# BLDC_driver_board_4_layer.net
KiCad netlist of a schematic drawn in EAGLE
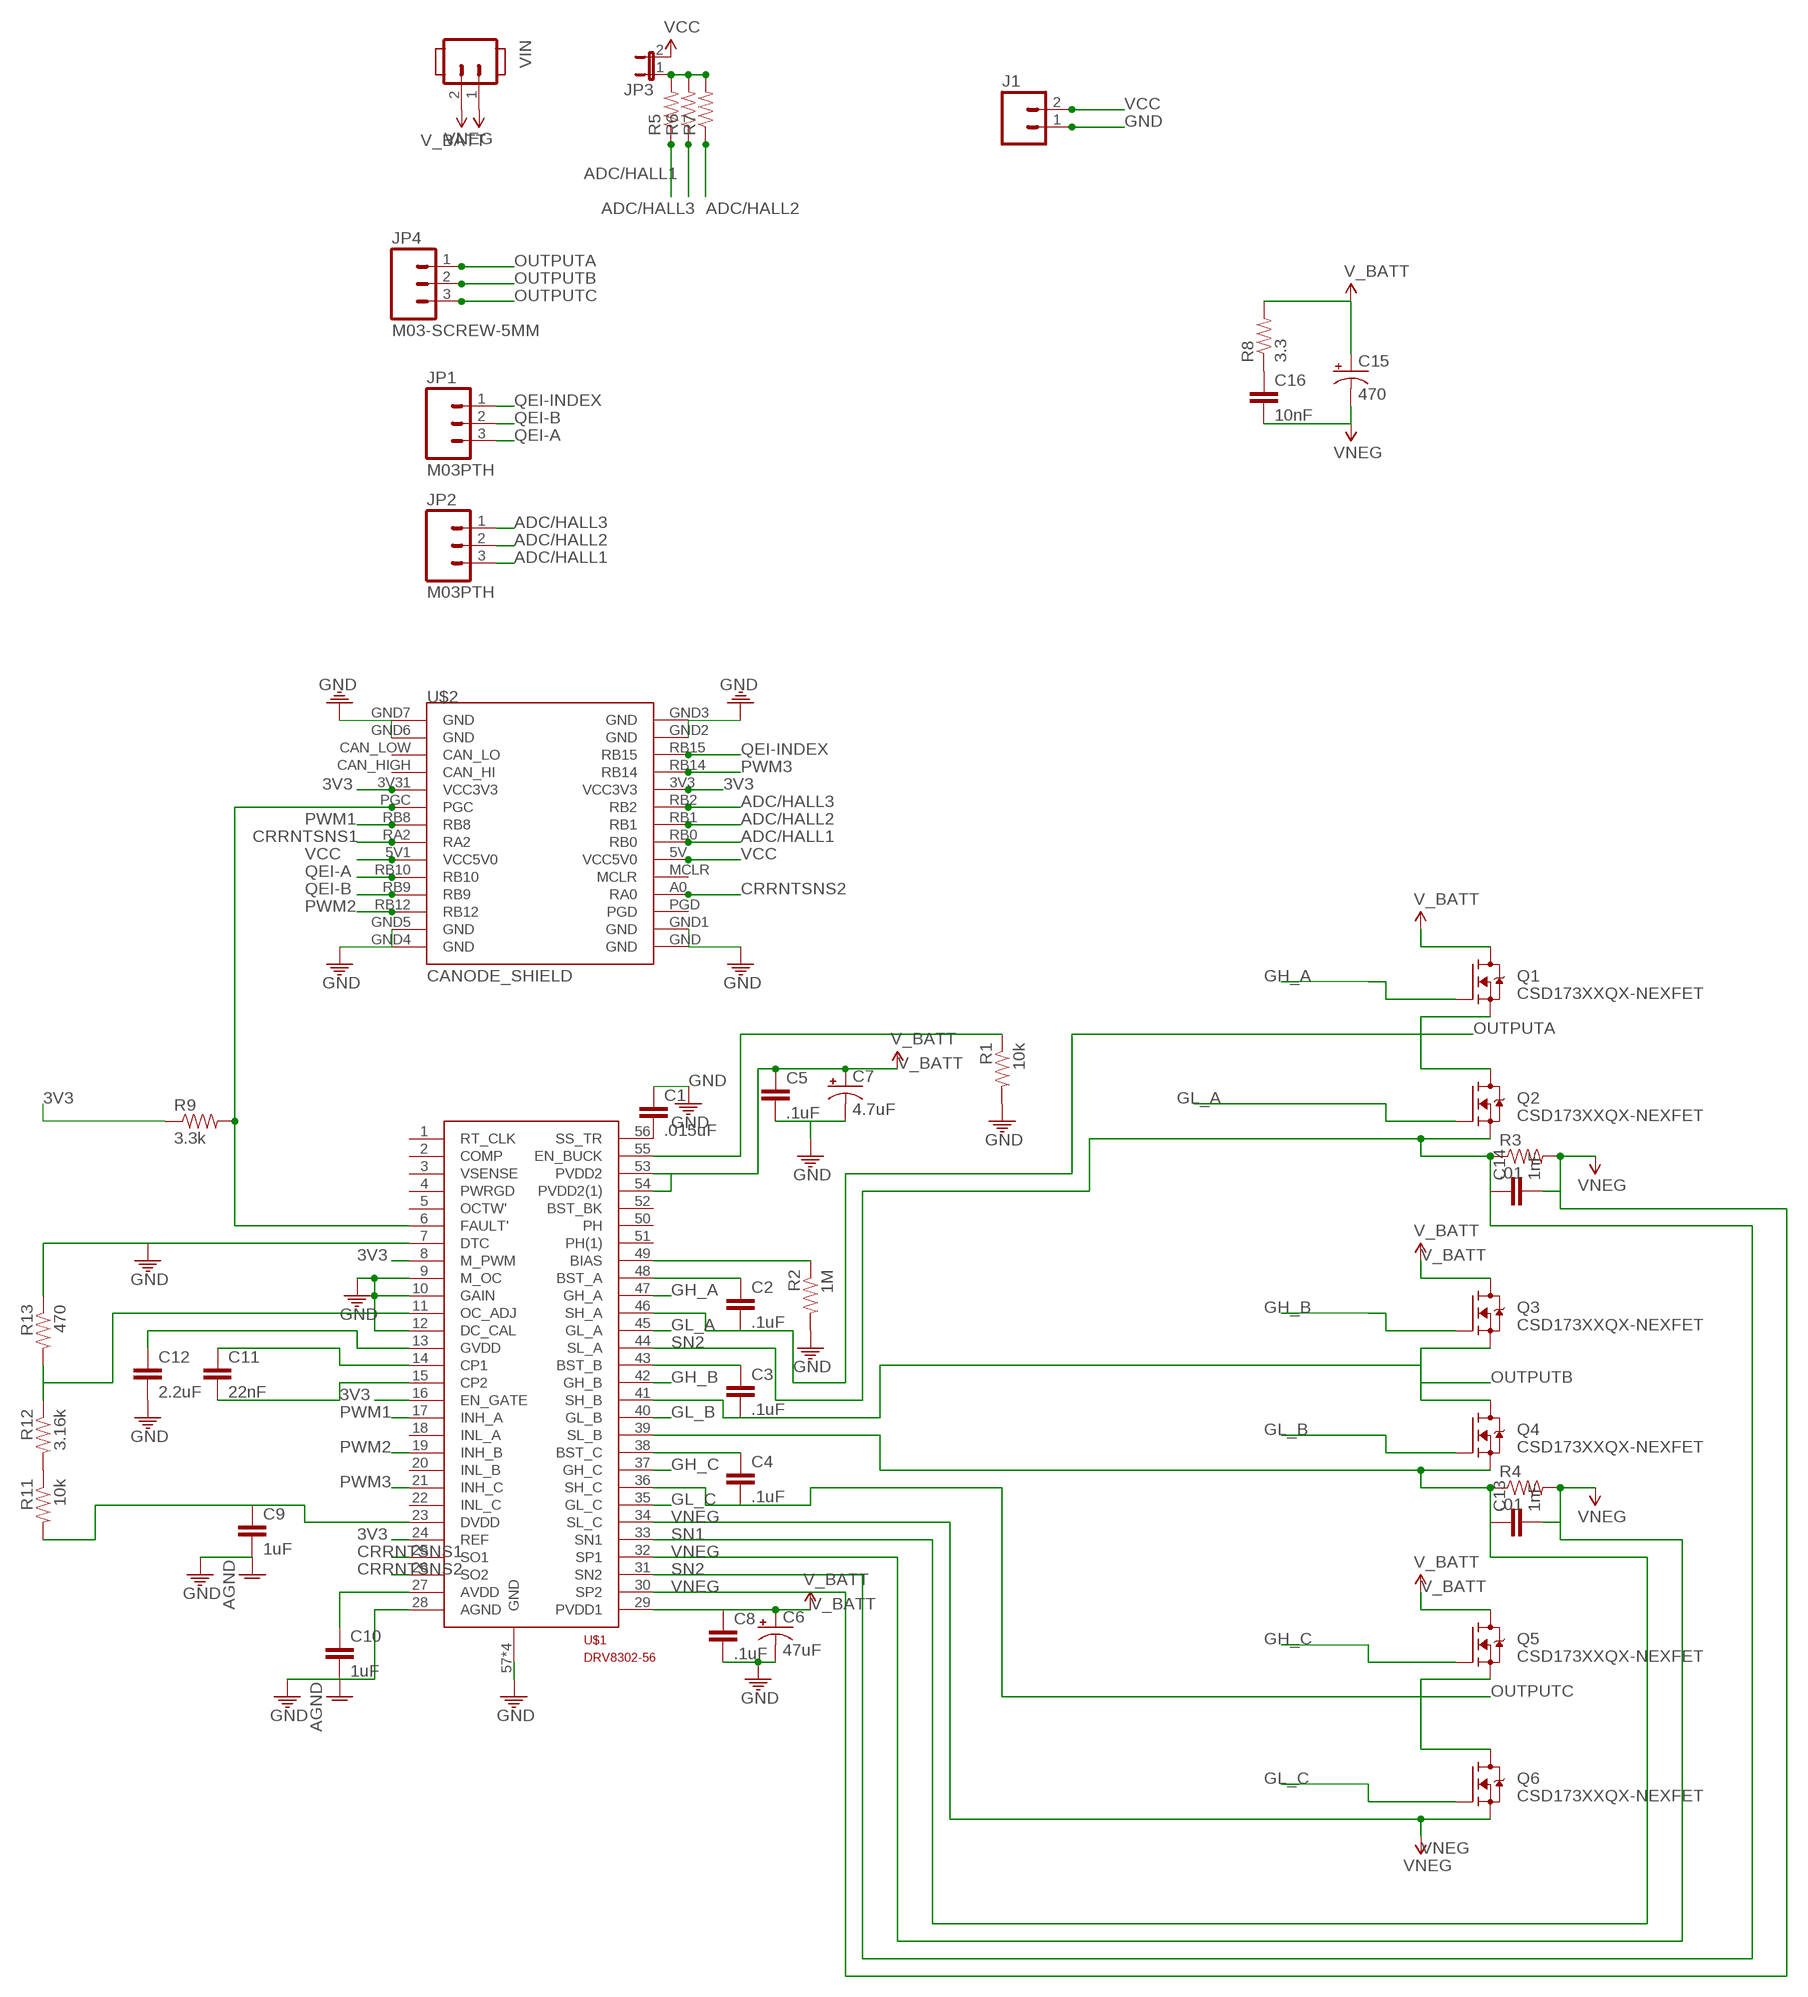
[diagram p0: schematic, sheet 1]

(export (version "E")
  (design (tool "Eeschema 10.0.6"))
  (components
    (comp (ref "C1")
      (value ".015uF")
      (footprint "eagle-import:1206")
      (libsource (lib "eagle-import") (part "CAP1206"))
    )
    (comp (ref "C2")
      (value ".1uF")
      (footprint "eagle-import:1206")
      (libsource (lib "eagle-import") (part "CAP1206"))
    )
    (comp (ref "C3")
      (value ".1uF")
      (footprint "eagle-import:1206")
      (libsource (lib "eagle-import") (part "CAP1206"))
    )
    (comp (ref "C4")
      (value ".1uF")
      (footprint "eagle-import:1206")
      (libsource (lib "eagle-import") (part "CAP1206"))
    )
    (comp (ref "C5")
      (value ".1uF")
      (footprint "eagle-import:1206")
      (libsource (lib "eagle-import") (part "CAP1206"))
    )
    (comp (ref "C6")
      (value "47uF")
      (footprint "eagle-import:CPOL-RADIAL-6.3MM")
      (libsource (lib "eagle-import") (part "pavlo_CAP_POL"))
    )
    (comp (ref "C7")
      (value "4.7uF")
      (footprint "eagle-import:CPOL-RADIA-5MM")
      (libsource (lib "eagle-import") (part "CAP_POLYO"))
    )
    (comp (ref "C8")
      (value ".1uF")
      (footprint "eagle-import:1206")
      (libsource (lib "eagle-import") (part "CAP1206"))
    )
    (comp (ref "C9")
      (value "1uF")
      (footprint "eagle-import:1206")
      (libsource (lib "eagle-import") (part "CAP1206"))
    )
    (comp (ref "C10")
      (value "1uF")
      (footprint "eagle-import:1206")
      (libsource (lib "eagle-import") (part "CAP1206"))
    )
    (comp (ref "C11")
      (value "22nF")
      (footprint "eagle-import:1206")
      (libsource (lib "eagle-import") (part "CAP1206"))
    )
    (comp (ref "C12")
      (value "2.2uF")
      (footprint "eagle-import:1206")
      (libsource (lib "eagle-import") (part "CAP1206"))
    )
    (comp (ref "C13")
      (value "1nF")
      (footprint "eagle-import:1206")
      (libsource (lib "eagle-import") (part "CAP1206"))
    )
    (comp (ref "C14")
      (value "1nF")
      (footprint "eagle-import:1206")
      (libsource (lib "eagle-import") (part "CAP1206"))
    )
    (comp (ref "C15")
      (value "470")
      (footprint "eagle-import:CPOL-RADIAL-1000UF-63V")
      (libsource (lib "eagle-import") (part "CAP_POLPTH3"))
    )
    (comp (ref "C16")
      (value "10nF")
      (footprint "eagle-import:1206")
      (libsource (lib "eagle-import") (part "CAP1206"))
    )
    (comp (ref "J1")
      (value "M02")
      (footprint "eagle-import:SOCKET-MALE-2.54MM-2")
      (libsource (lib "eagle-import") (part "M02"))
    )
    (comp (ref "JP1")
      (value "M03PTH")
      (footprint "eagle-import:1X03")
      (libsource (lib "eagle-import") (part "M03PTH"))
    )
    (comp (ref "JP2")
      (value "M03PTH")
      (footprint "eagle-import:1X03")
      (libsource (lib "eagle-import") (part "M03PTH"))
    )
    (comp (ref "JP3")
      (value "JP1E")
      (footprint "eagle-import:JP1")
      (libsource (lib "eagle-import") (part "JP1E"))
    )
    (comp (ref "JP4")
      (value "M03-SCREW-5MM")
      (footprint "eagle-import:SCREWTERMINAL-5MM-3")
      (libsource (lib "eagle-import") (part "M03-SCREW-5MM"))
    )
    (comp (ref "Q1")
      (value "CSD173XXQX-NEXFET")
      (footprint "eagle-import:CSD173XXQX")
      (libsource (lib "eagle-import") (part "CSD173XXQX-NEXFET"))
    )
    (comp (ref "Q2")
      (value "CSD173XXQX-NEXFET")
      (footprint "eagle-import:CSD173XXQX")
      (libsource (lib "eagle-import") (part "CSD173XXQX-NEXFET"))
    )
    (comp (ref "Q3")
      (value "CSD173XXQX-NEXFET")
      (footprint "eagle-import:CSD173XXQX")
      (libsource (lib "eagle-import") (part "CSD173XXQX-NEXFET"))
    )
    (comp (ref "Q4")
      (value "CSD173XXQX-NEXFET")
      (footprint "eagle-import:CSD173XXQX")
      (libsource (lib "eagle-import") (part "CSD173XXQX-NEXFET"))
    )
    (comp (ref "Q5")
      (value "CSD173XXQX-NEXFET")
      (footprint "eagle-import:CSD173XXQX")
      (libsource (lib "eagle-import") (part "CSD173XXQX-NEXFET"))
    )
    (comp (ref "Q6")
      (value "CSD173XXQX-NEXFET")
      (footprint "eagle-import:CSD173XXQX")
      (libsource (lib "eagle-import") (part "CSD173XXQX-NEXFET"))
    )
    (comp (ref "R1")
      (value "10k")
      (footprint "eagle-import:0805")
      (libsource (lib "eagle-import") (part "RESISTOR0805-RES"))
    )
    (comp (ref "R2")
      (value "1M")
      (footprint "eagle-import:0805")
      (libsource (lib "eagle-import") (part "RESISTOR0805-RES"))
    )
    (comp (ref "R3")
      (value ".01")
      (footprint "eagle-import:SMT-REF")
      (libsource (lib "eagle-import") (part "RESISTOR"))
    )
    (comp (ref "R4")
      (value ".01")
      (footprint "eagle-import:SMT-REF")
      (libsource (lib "eagle-import") (part "RESISTOR"))
    )
    (comp (ref "R5")
      (value "RESISTOR0805-RES")
      (footprint "eagle-import:0805")
      (libsource (lib "eagle-import") (part "RESISTOR0805-RES"))
    )
    (comp (ref "R6")
      (value "RESISTOR0805-RES")
      (footprint "eagle-import:0805")
      (libsource (lib "eagle-import") (part "RESISTOR0805-RES"))
    )
    (comp (ref "R7")
      (value "RESISTOR0805-RES")
      (footprint "eagle-import:0805")
      (libsource (lib "eagle-import") (part "RESISTOR0805-RES"))
    )
    (comp (ref "R8")
      (value "3.3")
      (footprint "eagle-import:1206")
      (libsource (lib "eagle-import") (part "CMPE118lib_RESISTOR1206"))
    )
    (comp (ref "R9")
      (value "3.3k")
      (footprint "eagle-import:0805")
      (libsource (lib "eagle-import") (part "RESISTOR0805-RES"))
    )
    (comp (ref "R11")
      (value "10k")
      (footprint "eagle-import:0805")
      (libsource (lib "eagle-import") (part "RESISTOR0805-RES"))
    )
    (comp (ref "R12")
      (value "3.16k")
      (footprint "eagle-import:0805")
      (libsource (lib "eagle-import") (part "RESISTOR0805-RES"))
    )
    (comp (ref "R13")
      (value "470")
      (footprint "eagle-import:0805")
      (libsource (lib "eagle-import") (part "RESISTOR0805-RES"))
    )
    (comp (ref "U$1")
      (value "DRV8302-56")
      (footprint "eagle-import:HTSSOP56")
      (libsource (lib "eagle-import") (part "DRV8302-56"))
    )
    (comp (ref "U$2")
      (value "CANODE_SHIELD")
      (footprint "eagle-import:CANODE_SHIELD")
      (libsource (lib "eagle-import") (part "CANODE_SHIELD"))
    )
    (comp (ref "VIN")
      (value "SCREWTERM02")
      (footprint "eagle-import:SCREW_TERMINAL-5.08MM-2")
      (libsource (lib "eagle-import") (part "SCREWTERM02"))
    )
  )
  (nets
    (net (code "1") (name "/3V3") (class "Default")
      (node (ref "R9") (pin "1") (pinfunction "1_1") (pintype "passive"))
      (node (ref "U$1") (pin "16") (pinfunction "EN_GATE_16") (pintype "bidirectional"))
      (node (ref "U$1") (pin "24") (pinfunction "REF_24") (pintype "bidirectional"))
      (node (ref "U$1") (pin "8") (pinfunction "M_PWM_8") (pintype "bidirectional"))
      (node (ref "U$2") (pin "3V3") (pinfunction "VCC3V3_3V3") (pintype "bidirectional"))
      (node (ref "U$2") (pin "3V31") (pinfunction "VCC3V3_3V31") (pintype "bidirectional"))
    )
    (net (code "2") (name "/ADC{slash}HALL1") (class "Default")
      (node (ref "JP2") (pin "3") (pinfunction "3_3") (pintype "passive"))
      (node (ref "R6") (pin "1") (pinfunction "1_1") (pintype "passive"))
      (node (ref "U$2") (pin "RB0") (pinfunction "RB0_RB0") (pintype "bidirectional"))
    )
    (net (code "3") (name "/ADC{slash}HALL2") (class "Default")
      (node (ref "JP2") (pin "2") (pinfunction "2_2") (pintype "passive"))
      (node (ref "R7") (pin "1") (pinfunction "1_1") (pintype "passive"))
      (node (ref "U$2") (pin "RB1") (pinfunction "RB1_RB1") (pintype "bidirectional"))
    )
    (net (code "4") (name "/ADC{slash}HALL3") (class "Default")
      (node (ref "JP2") (pin "1") (pinfunction "1_1") (pintype "passive"))
      (node (ref "R5") (pin "1") (pinfunction "1_1") (pintype "passive"))
      (node (ref "U$2") (pin "RB2") (pinfunction "RB2_RB2") (pintype "bidirectional"))
    )
    (net (code "5") (name "/CRRNTSNS1") (class "Default")
      (node (ref "U$1") (pin "25") (pinfunction "SO1_25") (pintype "bidirectional"))
      (node (ref "U$2") (pin "RA2") (pinfunction "RA2_RA2") (pintype "bidirectional"))
    )
    (net (code "6") (name "/CRRNTSNS2") (class "Default")
      (node (ref "U$1") (pin "26") (pinfunction "SO2_26") (pintype "bidirectional"))
      (node (ref "U$2") (pin "A0") (pinfunction "RA0_A0") (pintype "bidirectional"))
    )
    (net (code "7") (name "/GH_A") (class "Default")
      (node (ref "Q1") (pin "G") (pinfunction "G_G") (pintype "passive"))
      (node (ref "U$1") (pin "47") (pinfunction "GH_A_47") (pintype "bidirectional"))
    )
    (net (code "8") (name "/GH_B") (class "Default")
      (node (ref "Q3") (pin "G") (pinfunction "G_G") (pintype "passive"))
      (node (ref "U$1") (pin "42") (pinfunction "GH_B_42") (pintype "bidirectional"))
    )
    (net (code "9") (name "/GH_C") (class "Default")
      (node (ref "Q5") (pin "G") (pinfunction "G_G") (pintype "passive"))
      (node (ref "U$1") (pin "37") (pinfunction "GH_C_37") (pintype "bidirectional"))
    )
    (net (code "10") (name "/GL_A") (class "Default")
      (node (ref "Q2") (pin "G") (pinfunction "G_G") (pintype "passive"))
      (node (ref "U$1") (pin "45") (pinfunction "GL_A_45") (pintype "bidirectional"))
    )
    (net (code "11") (name "/GL_B") (class "Default")
      (node (ref "Q4") (pin "G") (pinfunction "G_G") (pintype "passive"))
      (node (ref "U$1") (pin "40") (pinfunction "GL_B_40") (pintype "bidirectional"))
    )
    (net (code "12") (name "/GL_C") (class "Default")
      (node (ref "Q6") (pin "G") (pinfunction "G_G") (pintype "passive"))
      (node (ref "U$1") (pin "35") (pinfunction "GL_C_35") (pintype "bidirectional"))
    )
    (net (code "13") (name "/OUTPUTA") (class "Default")
      (node (ref "C2") (pin "2") (pinfunction "2_2") (pintype "passive"))
      (node (ref "JP4") (pin "1") (pinfunction "1_1") (pintype "passive"))
      (node (ref "Q1") (pin "S1") (pinfunction "S_S1") (pintype "passive"))
      (node (ref "Q1") (pin "S2") (pinfunction "S_S2") (pintype "passive"))
      (node (ref "Q1") (pin "S3") (pinfunction "S_S3") (pintype "passive"))
      (node (ref "Q2") (pin "D") (pinfunction "D_D") (pintype "passive"))
      (node (ref "Q2") (pin "P$1") (pinfunction "D_P$1") (pintype "passive"))
      (node (ref "Q2") (pin "P$2") (pinfunction "D_P$2") (pintype "passive"))
      (node (ref "Q2") (pin "P$3") (pinfunction "D_P$3") (pintype "passive"))
      (node (ref "Q2") (pin "P$4") (pinfunction "D_P$4") (pintype "passive"))
      (node (ref "Q2") (pin "P$5") (pinfunction "D_P$5") (pintype "passive"))
      (node (ref "Q2") (pin "P$6") (pinfunction "D_P$6") (pintype "passive"))
      (node (ref "Q2") (pin "P$7") (pinfunction "D_P$7") (pintype "passive"))
      (node (ref "Q2") (pin "P$8") (pinfunction "D_P$8") (pintype "passive"))
      (node (ref "Q2") (pin "P$9") (pinfunction "D_P$9") (pintype "passive"))
      (node (ref "U$1") (pin "46") (pinfunction "SH_A_46") (pintype "bidirectional"))
    )
    (net (code "14") (name "/OUTPUTB") (class "Default")
      (node (ref "C3") (pin "2") (pinfunction "2_2") (pintype "passive"))
      (node (ref "JP4") (pin "2") (pinfunction "2_2") (pintype "passive"))
      (node (ref "Q3") (pin "S1") (pinfunction "S_S1") (pintype "passive"))
      (node (ref "Q3") (pin "S2") (pinfunction "S_S2") (pintype "passive"))
      (node (ref "Q3") (pin "S3") (pinfunction "S_S3") (pintype "passive"))
      (node (ref "Q4") (pin "D") (pinfunction "D_D") (pintype "passive"))
      (node (ref "Q4") (pin "P$1") (pinfunction "D_P$1") (pintype "passive"))
      (node (ref "Q4") (pin "P$2") (pinfunction "D_P$2") (pintype "passive"))
      (node (ref "Q4") (pin "P$3") (pinfunction "D_P$3") (pintype "passive"))
      (node (ref "Q4") (pin "P$4") (pinfunction "D_P$4") (pintype "passive"))
      (node (ref "Q4") (pin "P$5") (pinfunction "D_P$5") (pintype "passive"))
      (node (ref "Q4") (pin "P$6") (pinfunction "D_P$6") (pintype "passive"))
      (node (ref "Q4") (pin "P$7") (pinfunction "D_P$7") (pintype "passive"))
      (node (ref "Q4") (pin "P$8") (pinfunction "D_P$8") (pintype "passive"))
      (node (ref "Q4") (pin "P$9") (pinfunction "D_P$9") (pintype "passive"))
      (node (ref "U$1") (pin "41") (pinfunction "SH_B_41") (pintype "bidirectional"))
    )
    (net (code "15") (name "/OUTPUTC") (class "Default")
      (node (ref "C4") (pin "2") (pinfunction "2_2") (pintype "passive"))
      (node (ref "JP4") (pin "3") (pinfunction "3_3") (pintype "passive"))
      (node (ref "Q5") (pin "S1") (pinfunction "S_S1") (pintype "passive"))
      (node (ref "Q5") (pin "S2") (pinfunction "S_S2") (pintype "passive"))
      (node (ref "Q5") (pin "S3") (pinfunction "S_S3") (pintype "passive"))
      (node (ref "Q6") (pin "D") (pinfunction "D_D") (pintype "passive"))
      (node (ref "Q6") (pin "P$1") (pinfunction "D_P$1") (pintype "passive"))
      (node (ref "Q6") (pin "P$2") (pinfunction "D_P$2") (pintype "passive"))
      (node (ref "Q6") (pin "P$3") (pinfunction "D_P$3") (pintype "passive"))
      (node (ref "Q6") (pin "P$4") (pinfunction "D_P$4") (pintype "passive"))
      (node (ref "Q6") (pin "P$5") (pinfunction "D_P$5") (pintype "passive"))
      (node (ref "Q6") (pin "P$6") (pinfunction "D_P$6") (pintype "passive"))
      (node (ref "Q6") (pin "P$7") (pinfunction "D_P$7") (pintype "passive"))
      (node (ref "Q6") (pin "P$8") (pinfunction "D_P$8") (pintype "passive"))
      (node (ref "Q6") (pin "P$9") (pinfunction "D_P$9") (pintype "passive"))
      (node (ref "U$1") (pin "36") (pinfunction "SH_C_36") (pintype "bidirectional"))
    )
    (net (code "16") (name "/PWM1") (class "Default")
      (node (ref "U$1") (pin "17") (pinfunction "INH_A_17") (pintype "bidirectional"))
      (node (ref "U$2") (pin "RB8") (pinfunction "RB8_RB8") (pintype "bidirectional"))
    )
    (net (code "17") (name "/PWM2") (class "Default")
      (node (ref "U$1") (pin "19") (pinfunction "INH_B_19") (pintype "bidirectional"))
      (node (ref "U$2") (pin "RB12") (pinfunction "RB12_RB12") (pintype "bidirectional"))
    )
    (net (code "18") (name "/PWM3") (class "Default")
      (node (ref "U$1") (pin "21") (pinfunction "INH_C_21") (pintype "bidirectional"))
      (node (ref "U$2") (pin "RB14") (pinfunction "RB14_RB14") (pintype "bidirectional"))
    )
    (net (code "19") (name "/QEI-A") (class "Default")
      (node (ref "JP1") (pin "3") (pinfunction "3_3") (pintype "passive"))
      (node (ref "U$2") (pin "RB10") (pinfunction "RB10_RB10") (pintype "bidirectional"))
    )
    (net (code "20") (name "/QEI-B") (class "Default")
      (node (ref "JP1") (pin "2") (pinfunction "2_2") (pintype "passive"))
      (node (ref "U$2") (pin "RB9") (pinfunction "RB9_RB9") (pintype "bidirectional"))
    )
    (net (code "21") (name "/QEI-INDEX") (class "Default")
      (node (ref "JP1") (pin "1") (pinfunction "1_1") (pintype "passive"))
      (node (ref "U$2") (pin "RB15") (pinfunction "RB15_RB15") (pintype "bidirectional"))
    )
    (net (code "22") (name "/SN1") (class "Default")
      (node (ref "C13") (pin "1") (pinfunction "1_1") (pintype "passive"))
      (node (ref "Q4") (pin "S1") (pinfunction "S_S1") (pintype "passive"))
      (node (ref "Q4") (pin "S2") (pinfunction "S_S2") (pintype "passive"))
      (node (ref "Q4") (pin "S3") (pinfunction "S_S3") (pintype "passive"))
      (node (ref "R4") (pin "1") (pinfunction "1_1") (pintype "passive"))
      (node (ref "R4") (pin "P$10") (pinfunction "1_P$10") (pintype "passive"))
      (node (ref "R4") (pin "P$11") (pinfunction "1_P$11") (pintype "passive"))
      (node (ref "R4") (pin "P$12") (pinfunction "1_P$12") (pintype "passive"))
      (node (ref "R4") (pin "P$7") (pinfunction "1_P$7") (pintype "passive"))
      (node (ref "R4") (pin "P$8") (pinfunction "1_P$8") (pintype "passive"))
      (node (ref "R4") (pin "P$9") (pinfunction "1_P$9") (pintype "passive"))
      (node (ref "U$1") (pin "33") (pinfunction "SN1_33") (pintype "bidirectional"))
      (node (ref "U$1") (pin "39") (pinfunction "SL_B_39") (pintype "bidirectional"))
    )
    (net (code "23") (name "/SN2") (class "Default")
      (node (ref "C14") (pin "1") (pinfunction "1_1") (pintype "passive"))
      (node (ref "Q2") (pin "S1") (pinfunction "S_S1") (pintype "passive"))
      (node (ref "Q2") (pin "S2") (pinfunction "S_S2") (pintype "passive"))
      (node (ref "Q2") (pin "S3") (pinfunction "S_S3") (pintype "passive"))
      (node (ref "R3") (pin "1") (pinfunction "1_1") (pintype "passive"))
      (node (ref "R3") (pin "P$10") (pinfunction "1_P$10") (pintype "passive"))
      (node (ref "R3") (pin "P$11") (pinfunction "1_P$11") (pintype "passive"))
      (node (ref "R3") (pin "P$12") (pinfunction "1_P$12") (pintype "passive"))
      (node (ref "R3") (pin "P$7") (pinfunction "1_P$7") (pintype "passive"))
      (node (ref "R3") (pin "P$8") (pinfunction "1_P$8") (pintype "passive"))
      (node (ref "R3") (pin "P$9") (pinfunction "1_P$9") (pintype "passive"))
      (node (ref "U$1") (pin "31") (pinfunction "SN2_31") (pintype "bidirectional"))
      (node (ref "U$1") (pin "44") (pinfunction "SL_A_44") (pintype "bidirectional"))
    )
    (net (code "24") (name "AGND") (class "Default")
      (node (ref "C1") (pin "1") (pinfunction "1_1") (pintype "passive"))
      (node (ref "C10") (pin "2") (pinfunction "2_2") (pintype "passive"))
      (node (ref "C12") (pin "2") (pinfunction "2_2") (pintype "passive"))
      (node (ref "C5") (pin "2") (pinfunction "2_2") (pintype "passive"))
      (node (ref "C6") (pin "2") (pinfunction "-_2") (pintype "passive"))
      (node (ref "C7") (pin "2") (pinfunction "-_2") (pintype "passive"))
      (node (ref "C8") (pin "2") (pinfunction "2_2") (pintype "passive"))
      (node (ref "C9") (pin "2") (pinfunction "2_2") (pintype "passive"))
      (node (ref "J1") (pin "1") (pinfunction "1_1") (pintype "passive"))
      (node (ref "R1") (pin "2") (pinfunction "2_2") (pintype "passive"))
      (node (ref "R13") (pin "1") (pinfunction "1_1") (pintype "passive"))
      (node (ref "R2") (pin "2") (pinfunction "2_2") (pintype "passive"))
      (node (ref "U$1") (pin "10") (pinfunction "GAIN_10") (pintype "bidirectional"))
      (node (ref "U$1") (pin "12") (pinfunction "DC_CAL_12") (pintype "bidirectional"))
      (node (ref "U$1") (pin "28") (pinfunction "AGND_28") (pintype "bidirectional"))
      (node (ref "U$1") (pin "57") (pinfunction "GND_57") (pintype "bidirectional"))
      (node (ref "U$1") (pin "7") (pinfunction "DTC_7") (pintype "bidirectional"))
      (node (ref "U$1") (pin "9") (pinfunction "M_OC_9") (pintype "bidirectional"))
      (node (ref "U$1") (pin "P$1") (pinfunction "GND_P$1") (pintype "bidirectional"))
      (node (ref "U$1") (pin "P$2") (pinfunction "GND_P$2") (pintype "bidirectional"))
      (node (ref "U$1") (pin "P$3") (pinfunction "GND_P$3") (pintype "bidirectional"))
      (node (ref "U$2") (pin "GND") (pinfunction "GND_GND") (pintype "bidirectional"))
      (node (ref "U$2") (pin "GND1") (pinfunction "GND_GND1") (pintype "bidirectional"))
      (node (ref "U$2") (pin "GND2") (pinfunction "GND_GND2") (pintype "bidirectional"))
      (node (ref "U$2") (pin "GND3") (pinfunction "GND_GND3") (pintype "bidirectional"))
      (node (ref "U$2") (pin "GND4") (pinfunction "GND_GND4") (pintype "bidirectional"))
      (node (ref "U$2") (pin "GND5") (pinfunction "GND_GND5") (pintype "bidirectional"))
      (node (ref "U$2") (pin "GND6") (pinfunction "GND_GND6") (pintype "bidirectional"))
      (node (ref "U$2") (pin "GND7") (pinfunction "GND_GND7") (pintype "bidirectional"))
    )
    (net (code "25") (name "Net-(C16-Pad1)") (class "Default")
      (node (ref "C16") (pin "1") (pinfunction "1_1") (pintype "passive"))
      (node (ref "R8") (pin "1") (pinfunction "1_1") (pintype "passive"))
    )
    (net (code "26") (name "Net-(JP3-Pad1)") (class "Default")
      (node (ref "JP3") (pin "1") (pinfunction "1_1") (pintype "passive"))
      (node (ref "R5") (pin "2") (pinfunction "2_2") (pintype "passive"))
      (node (ref "R6") (pin "2") (pinfunction "2_2") (pintype "passive"))
      (node (ref "R7") (pin "2") (pinfunction "2_2") (pintype "passive"))
    )
    (net (code "27") (name "Net-(R11-Pad1)") (class "Default")
      (node (ref "R11") (pin "1") (pinfunction "1_1") (pintype "passive"))
      (node (ref "R12") (pin "2") (pinfunction "2_2") (pintype "passive"))
    )
    (net (code "28") (name "Net-(U$1-AVDD)") (class "Default")
      (node (ref "C10") (pin "1") (pinfunction "1_1") (pintype "passive"))
      (node (ref "U$1") (pin "27") (pinfunction "AVDD_27") (pintype "bidirectional"))
    )
    (net (code "29") (name "Net-(U$1-BIAS)") (class "Default")
      (node (ref "R2") (pin "1") (pinfunction "1_1") (pintype "passive"))
      (node (ref "U$1") (pin "49") (pinfunction "BIAS_49") (pintype "bidirectional"))
    )
    (net (code "30") (name "Net-(U$1-BST_A)") (class "Default")
      (node (ref "C2") (pin "1") (pinfunction "1_1") (pintype "passive"))
      (node (ref "U$1") (pin "48") (pinfunction "BST_A_48") (pintype "bidirectional"))
    )
    (net (code "31") (name "Net-(U$1-BST_B)") (class "Default")
      (node (ref "C3") (pin "1") (pinfunction "1_1") (pintype "passive"))
      (node (ref "U$1") (pin "43") (pinfunction "BST_B_43") (pintype "bidirectional"))
    )
    (net (code "32") (name "Net-(U$1-BST_C)") (class "Default")
      (node (ref "C4") (pin "1") (pinfunction "1_1") (pintype "passive"))
      (node (ref "U$1") (pin "38") (pinfunction "BST_C_38") (pintype "bidirectional"))
    )
    (net (code "33") (name "Net-(U$1-CP1)") (class "Default")
      (node (ref "C11") (pin "1") (pinfunction "1_1") (pintype "passive"))
      (node (ref "U$1") (pin "14") (pinfunction "CP1_14") (pintype "bidirectional"))
    )
    (net (code "34") (name "Net-(U$1-CP2)") (class "Default")
      (node (ref "C11") (pin "2") (pinfunction "2_2") (pintype "passive"))
      (node (ref "U$1") (pin "15") (pinfunction "CP2_15") (pintype "bidirectional"))
    )
    (net (code "35") (name "Net-(U$1-DVDD)") (class "Default")
      (node (ref "C9") (pin "1") (pinfunction "1_1") (pintype "passive"))
      (node (ref "R11") (pin "2") (pinfunction "2_2") (pintype "passive"))
      (node (ref "U$1") (pin "23") (pinfunction "DVDD_23") (pintype "bidirectional"))
    )
    (net (code "36") (name "Net-(U$1-EN_BUCK)") (class "Default")
      (node (ref "R1") (pin "1") (pinfunction "1_1") (pintype "passive"))
      (node (ref "U$1") (pin "55") (pinfunction "EN_BUCK_55") (pintype "bidirectional"))
    )
    (net (code "37") (name "Net-(U$1-FAULT')") (class "Default")
      (node (ref "R9") (pin "2") (pinfunction "2_2") (pintype "passive"))
      (node (ref "U$1") (pin "6") (pinfunction "FAULT'_6") (pintype "bidirectional"))
      (node (ref "U$2") (pin "PGC") (pinfunction "PGC_PGC") (pintype "bidirectional"))
    )
    (net (code "38") (name "Net-(U$1-GVDD)") (class "Default")
      (node (ref "C12") (pin "1") (pinfunction "1_1") (pintype "passive"))
      (node (ref "U$1") (pin "13") (pinfunction "GVDD_13") (pintype "bidirectional"))
    )
    (net (code "39") (name "Net-(U$1-OC_ADJ)") (class "Default")
      (node (ref "R12") (pin "1") (pinfunction "1_1") (pintype "passive"))
      (node (ref "R13") (pin "2") (pinfunction "2_2") (pintype "passive"))
      (node (ref "U$1") (pin "11") (pinfunction "OC_ADJ_11") (pintype "bidirectional"))
    )
    (net (code "40") (name "Net-(U$1-SS_TR)") (class "Default")
      (node (ref "C1") (pin "2") (pinfunction "2_2") (pintype "passive"))
      (node (ref "U$1") (pin "56") (pinfunction "SS_TR_56") (pintype "bidirectional"))
    )
    (net (code "41") (name "VCC") (class "Default")
      (node (ref "J1") (pin "2") (pinfunction "2_2") (pintype "passive"))
      (node (ref "JP3") (pin "2") (pinfunction "2_2") (pintype "passive"))
      (node (ref "U$2") (pin "5V") (pinfunction "VCC5V0_5V") (pintype "bidirectional"))
      (node (ref "U$2") (pin "5V1") (pinfunction "VCC5V0_5V1") (pintype "bidirectional"))
    )
    (net (code "42") (name "VNEG") (class "Default")
      (node (ref "C13") (pin "2") (pinfunction "2_2") (pintype "passive"))
      (node (ref "C14") (pin "2") (pinfunction "2_2") (pintype "passive"))
      (node (ref "C15") (pin "2") (pinfunction "-_2") (pintype "passive"))
      (node (ref "C16") (pin "2") (pinfunction "2_2") (pintype "passive"))
      (node (ref "Q6") (pin "S1") (pinfunction "S_S1") (pintype "passive"))
      (node (ref "Q6") (pin "S2") (pinfunction "S_S2") (pintype "passive"))
      (node (ref "Q6") (pin "S3") (pinfunction "S_S3") (pintype "passive"))
      (node (ref "R3") (pin "2") (pinfunction "2_2") (pintype "passive"))
      (node (ref "R3") (pin "P$1") (pinfunction "2_P$1") (pintype "passive"))
      (node (ref "R3") (pin "P$2") (pinfunction "2_P$2") (pintype "passive"))
      (node (ref "R3") (pin "P$3") (pinfunction "2_P$3") (pintype "passive"))
      (node (ref "R3") (pin "P$4") (pinfunction "2_P$4") (pintype "passive"))
      (node (ref "R3") (pin "P$5") (pinfunction "2_P$5") (pintype "passive"))
      (node (ref "R3") (pin "P$6") (pinfunction "2_P$6") (pintype "passive"))
      (node (ref "R4") (pin "2") (pinfunction "2_2") (pintype "passive"))
      (node (ref "R4") (pin "P$1") (pinfunction "2_P$1") (pintype "passive"))
      (node (ref "R4") (pin "P$2") (pinfunction "2_P$2") (pintype "passive"))
      (node (ref "R4") (pin "P$3") (pinfunction "2_P$3") (pintype "passive"))
      (node (ref "R4") (pin "P$4") (pinfunction "2_P$4") (pintype "passive"))
      (node (ref "R4") (pin "P$5") (pinfunction "2_P$5") (pintype "passive"))
      (node (ref "R4") (pin "P$6") (pinfunction "2_P$6") (pintype "passive"))
      (node (ref "U$1") (pin "30") (pinfunction "SP2_30") (pintype "bidirectional"))
      (node (ref "U$1") (pin "32") (pinfunction "SP1_32") (pintype "bidirectional"))
      (node (ref "U$1") (pin "34") (pinfunction "SL_C_34") (pintype "bidirectional"))
      (node (ref "VIN") (pin "2") (pinfunction "2_2") (pintype "passive"))
    )
    (net (code "43") (name "V_BATT") (class "Default")
      (node (ref "C15") (pin "1") (pinfunction "+_1") (pintype "passive"))
      (node (ref "C5") (pin "1") (pinfunction "1_1") (pintype "passive"))
      (node (ref "C6") (pin "1") (pinfunction "+_1") (pintype "passive"))
      (node (ref "C7") (pin "1") (pinfunction "+_1") (pintype "passive"))
      (node (ref "C8") (pin "1") (pinfunction "1_1") (pintype "passive"))
      (node (ref "Q1") (pin "D") (pinfunction "D_D") (pintype "passive"))
      (node (ref "Q1") (pin "P$1") (pinfunction "D_P$1") (pintype "passive"))
      (node (ref "Q1") (pin "P$2") (pinfunction "D_P$2") (pintype "passive"))
      (node (ref "Q1") (pin "P$3") (pinfunction "D_P$3") (pintype "passive"))
      (node (ref "Q1") (pin "P$4") (pinfunction "D_P$4") (pintype "passive"))
      (node (ref "Q1") (pin "P$5") (pinfunction "D_P$5") (pintype "passive"))
      (node (ref "Q1") (pin "P$6") (pinfunction "D_P$6") (pintype "passive"))
      (node (ref "Q1") (pin "P$7") (pinfunction "D_P$7") (pintype "passive"))
      (node (ref "Q1") (pin "P$8") (pinfunction "D_P$8") (pintype "passive"))
      (node (ref "Q1") (pin "P$9") (pinfunction "D_P$9") (pintype "passive"))
      (node (ref "Q3") (pin "D") (pinfunction "D_D") (pintype "passive"))
      (node (ref "Q3") (pin "P$1") (pinfunction "D_P$1") (pintype "passive"))
      (node (ref "Q3") (pin "P$2") (pinfunction "D_P$2") (pintype "passive"))
      (node (ref "Q3") (pin "P$3") (pinfunction "D_P$3") (pintype "passive"))
      (node (ref "Q3") (pin "P$4") (pinfunction "D_P$4") (pintype "passive"))
      (node (ref "Q3") (pin "P$5") (pinfunction "D_P$5") (pintype "passive"))
      (node (ref "Q3") (pin "P$6") (pinfunction "D_P$6") (pintype "passive"))
      (node (ref "Q3") (pin "P$7") (pinfunction "D_P$7") (pintype "passive"))
      (node (ref "Q3") (pin "P$8") (pinfunction "D_P$8") (pintype "passive"))
      (node (ref "Q3") (pin "P$9") (pinfunction "D_P$9") (pintype "passive"))
      (node (ref "Q5") (pin "D") (pinfunction "D_D") (pintype "passive"))
      (node (ref "Q5") (pin "P$1") (pinfunction "D_P$1") (pintype "passive"))
      (node (ref "Q5") (pin "P$2") (pinfunction "D_P$2") (pintype "passive"))
      (node (ref "Q5") (pin "P$3") (pinfunction "D_P$3") (pintype "passive"))
      (node (ref "Q5") (pin "P$4") (pinfunction "D_P$4") (pintype "passive"))
      (node (ref "Q5") (pin "P$5") (pinfunction "D_P$5") (pintype "passive"))
      (node (ref "Q5") (pin "P$6") (pinfunction "D_P$6") (pintype "passive"))
      (node (ref "Q5") (pin "P$7") (pinfunction "D_P$7") (pintype "passive"))
      (node (ref "Q5") (pin "P$8") (pinfunction "D_P$8") (pintype "passive"))
      (node (ref "Q5") (pin "P$9") (pinfunction "D_P$9") (pintype "passive"))
      (node (ref "R8") (pin "2") (pinfunction "2_2") (pintype "passive"))
      (node (ref "U$1") (pin "29") (pinfunction "PVDD1_29") (pintype "bidirectional"))
      (node (ref "U$1") (pin "53") (pinfunction "PVDD2_53") (pintype "bidirectional"))
      (node (ref "U$1") (pin "54") (pinfunction "PVDD2(1)_54") (pintype "bidirectional"))
      (node (ref "VIN") (pin "1") (pinfunction "1_1") (pintype "passive"))
    )
    (net (code "44") (name "unconnected-(U$1-BST_BK-Pad52)") (class "Default")
      (node (ref "U$1") (pin "52") (pinfunction "BST_BK_52") (pintype "bidirectional"))
    )
    (net (code "45") (name "unconnected-(U$1-COMP-Pad2)") (class "Default")
      (node (ref "U$1") (pin "2") (pinfunction "COMP_2") (pintype "bidirectional"))
    )
    (net (code "46") (name "unconnected-(U$1-INL_A-Pad18)") (class "Default")
      (node (ref "U$1") (pin "18") (pinfunction "INL_A_18") (pintype "bidirectional"))
    )
    (net (code "47") (name "unconnected-(U$1-INL_B-Pad20)") (class "Default")
      (node (ref "U$1") (pin "20") (pinfunction "INL_B_20") (pintype "bidirectional"))
    )
    (net (code "48") (name "unconnected-(U$1-INL_C-Pad22)") (class "Default")
      (node (ref "U$1") (pin "22") (pinfunction "INL_C_22") (pintype "bidirectional"))
    )
    (net (code "49") (name "unconnected-(U$1-OCTW'-Pad5)") (class "Default")
      (node (ref "U$1") (pin "5") (pinfunction "OCTW'_5") (pintype "bidirectional"))
    )
    (net (code "50") (name "unconnected-(U$1-PH(1)-Pad51)") (class "Default")
      (node (ref "U$1") (pin "51") (pinfunction "PH(1)_51") (pintype "bidirectional"))
    )
    (net (code "51") (name "unconnected-(U$1-PH-Pad50)") (class "Default")
      (node (ref "U$1") (pin "50") (pinfunction "PH_50") (pintype "bidirectional"))
    )
    (net (code "52") (name "unconnected-(U$1-PWRGD-Pad4)") (class "Default")
      (node (ref "U$1") (pin "4") (pinfunction "PWRGD_4") (pintype "bidirectional"))
    )
    (net (code "53") (name "unconnected-(U$1-RT_CLK-Pad1)") (class "Default")
      (node (ref "U$1") (pin "1") (pinfunction "RT_CLK_1") (pintype "bidirectional"))
    )
    (net (code "54") (name "unconnected-(U$1-VSENSE-Pad3)") (class "Default")
      (node (ref "U$1") (pin "3") (pinfunction "VSENSE_3") (pintype "bidirectional"))
    )
    (net (code "55") (name "unconnected-(U$2-CAN_HI-PadCAN_HIGH)") (class "Default")
      (node (ref "U$2") (pin "CAN_HIGH") (pinfunction "CAN_HI_CAN_HIGH") (pintype "bidirectional"))
    )
    (net (code "56") (name "unconnected-(U$2-CAN_LO-PadCAN_LOW)") (class "Default")
      (node (ref "U$2") (pin "CAN_LOW") (pinfunction "CAN_LO_CAN_LOW") (pintype "bidirectional"))
    )
    (net (code "57") (name "unconnected-(U$2-PadMCLR)") (class "Default")
      (node (ref "U$2") (pin "MCLR") (pinfunction "MCLR_MCLR") (pintype "bidirectional"))
    )
    (net (code "58") (name "unconnected-(U$2-PadPGD)") (class "Default")
      (node (ref "U$2") (pin "PGD") (pinfunction "PGD_PGD") (pintype "bidirectional"))
    )
  )
)
